# contact_control_board.net
KiCad netlist of a schematic drawn in EAGLE
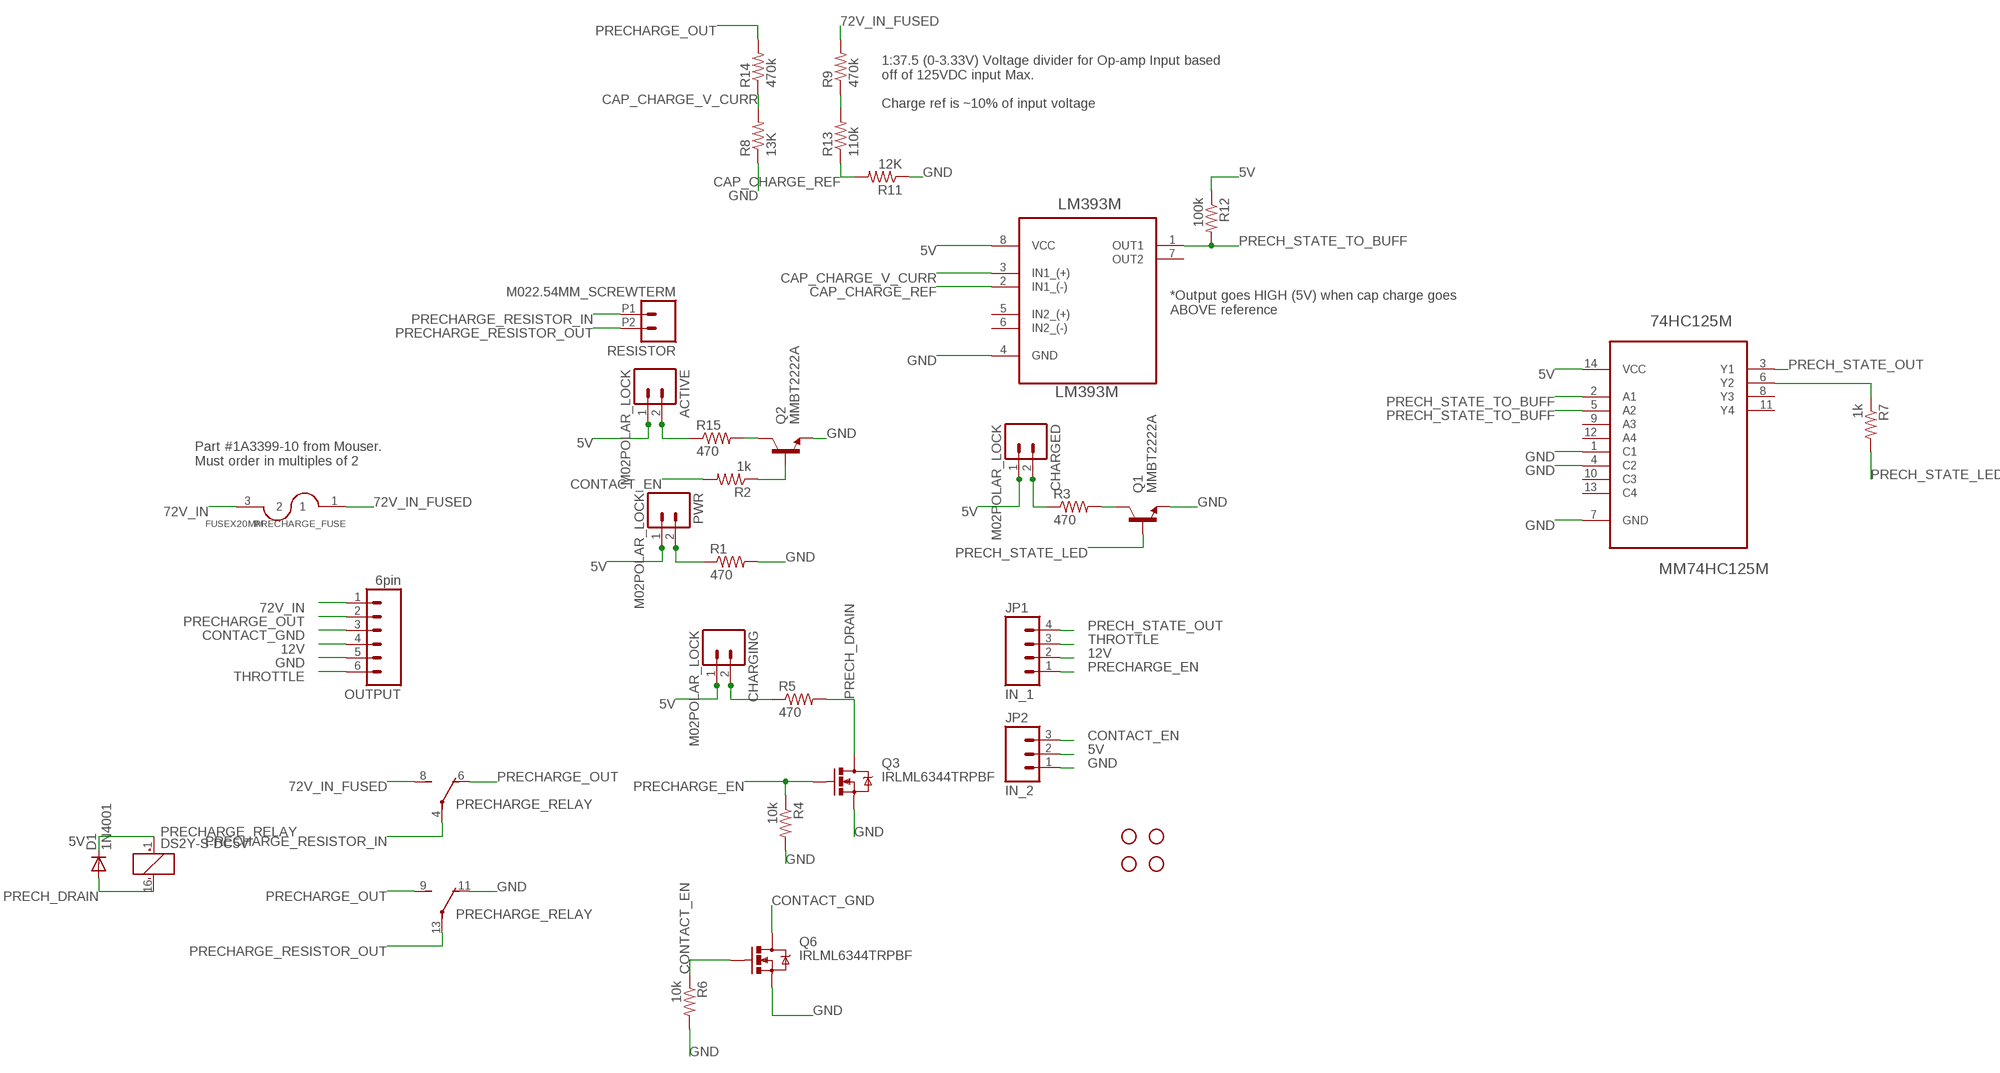
[diagram p0: schematic, sheet 1]

(export (version "E")
  (design (tool "Eeschema 10.0.6"))
  (components
    (comp (ref "74HC125M")
      (value "MM74HC125M")
      (footprint "eagle-import:SOIC127P600X175-14N")
      (libsource (lib "eagle-import") (part "MM74HC125M"))
    )
    (comp (ref "ACTIVE")
      (value "M02POLAR_LOCK")
      (footprint "eagle-import:MOLEX-1X2_LOCK")
      (libsource (lib "eagle-import") (part "M02POLAR_LOCK"))
    )
    (comp (ref "CHARGED")
      (value "M02POLAR_LOCK")
      (footprint "eagle-import:MOLEX-1X2_LOCK")
      (libsource (lib "eagle-import") (part "M02POLAR_LOCK"))
    )
    (comp (ref "CHARGING")
      (value "M02POLAR_LOCK")
      (footprint "eagle-import:MOLEX-1X2_LOCK")
      (libsource (lib "eagle-import") (part "M02POLAR_LOCK"))
    )
    (comp (ref "D1")
      (value "1N4001")
      (footprint "eagle-import:DIODE-1N4001")
      (libsource (lib "eagle-import") (part "DIODEPTH"))
    )
    (comp (ref "JP1")
      (value "IN_1")
      (footprint "eagle-import:MOLEX-1X4_LOCK")
      (libsource (lib "eagle-import") (part "M04POLAR_LOCK"))
    )
    (comp (ref "JP2")
      (value "IN_2")
      (footprint "eagle-import:MOLEX-1X3_LOCK")
      (libsource (lib "eagle-import") (part "M03POLAR_LOCK"))
    )
    (comp (ref "LM393M")
      (value "LM393M")
      (footprint "eagle-import:SOIC127P600X180-8N")
      (libsource (lib "eagle-import") (part "LM393M"))
    )
    (comp (ref "OUTPUT")
      (value "6pin")
      (footprint "eagle-import:SCREWTERMINAL-3.5MM-6")
      (libsource (lib "eagle-import") (part "M063.5MM-6"))
    )
    (comp (ref "PRECHARGE_FUSE")
      (value "FUSEX20MM")
      (footprint "eagle-import:FUSE_5MM")
      (libsource (lib "eagle-import") (part "FUSEX20MM"))
    )
    (comp (ref "PRECHARGE_RELAY")
      (value "DS2Y-S-DC5V")
      (footprint "eagle-import:DS2Y")
      (libsource (lib "eagle-import") (part "DS2Y-S-DC5V"))
    )
    (comp (ref "PWR")
      (value "M02POLAR_LOCK")
      (footprint "eagle-import:MOLEX-1X2_LOCK")
      (libsource (lib "eagle-import") (part "M02POLAR_LOCK"))
    )
    (comp (ref "Q1")
      (value "MMBT2222A")
      (footprint "eagle-import:SOT23")
      (libsource (lib "eagle-import") (part "TRANSISTOR_NPNMMBT2222A"))
    )
    (comp (ref "Q2")
      (value "MMBT2222A")
      (footprint "eagle-import:SOT23")
      (libsource (lib "eagle-import") (part "TRANSISTOR_NPNMMBT2222A"))
    )
    (comp (ref "Q3")
      (value "IRLML6344TRPBF")
      (footprint "eagle-import:SOT23")
      (libsource (lib "eagle-import") (part "MOSFET-NCHANNELBSS123LT1G"))
    )
    (comp (ref "Q6")
      (value "IRLML6344TRPBF")
      (footprint "eagle-import:SOT23")
      (libsource (lib "eagle-import") (part "MOSFET-NCHANNELBSS123LT1G"))
    )
    (comp (ref "R1")
      (value "470")
      (footprint "eagle-import:0805")
      (libsource (lib "eagle-import") (part "RESISTOR0805-RES"))
    )
    (comp (ref "R2")
      (value "1k")
      (footprint "eagle-import:0603-RES")
      (libsource (lib "eagle-import") (part "RESISTOR0603-RES"))
    )
    (comp (ref "R3")
      (value "470")
      (footprint "eagle-import:0805")
      (libsource (lib "eagle-import") (part "RESISTOR0805-RES"))
    )
    (comp (ref "R4")
      (value "10k")
      (footprint "eagle-import:0603-RES")
      (libsource (lib "eagle-import") (part "RESISTOR0603-RES"))
    )
    (comp (ref "R5")
      (value "470")
      (footprint "eagle-import:0805")
      (libsource (lib "eagle-import") (part "RESISTOR0805-RES"))
    )
    (comp (ref "R6")
      (value "10k")
      (footprint "eagle-import:0603-RES")
      (libsource (lib "eagle-import") (part "RESISTOR0603-RES"))
    )
    (comp (ref "R7")
      (value "1k")
      (footprint "eagle-import:0603-RES")
      (libsource (lib "eagle-import") (part "RESISTOR0603-RES"))
    )
    (comp (ref "R8")
      (value "13K")
      (footprint "eagle-import:0805")
      (libsource (lib "eagle-import") (part "RESISTOR0805-RES"))
    )
    (comp (ref "R9")
      (value "470k")
      (footprint "eagle-import:0805")
      (libsource (lib "eagle-import") (part "RESISTOR0805-RES"))
    )
    (comp (ref "R11")
      (value "12K")
      (footprint "eagle-import:0805")
      (libsource (lib "eagle-import") (part "RESISTOR0805-RES"))
    )
    (comp (ref "R12")
      (value "100k")
      (footprint "eagle-import:0603-RES")
      (libsource (lib "eagle-import") (part "RESISTOR0603-RES"))
    )
    (comp (ref "R13")
      (value "110k")
      (footprint "eagle-import:0805")
      (libsource (lib "eagle-import") (part "RESISTOR0805-RES"))
    )
    (comp (ref "R14")
      (value "470k")
      (footprint "eagle-import:0805")
      (libsource (lib "eagle-import") (part "RESISTOR0805-RES"))
    )
    (comp (ref "R15")
      (value "470")
      (footprint "eagle-import:0805")
      (libsource (lib "eagle-import") (part "RESISTOR0805-RES"))
    )
    (comp (ref "RESISTOR")
      (value "M022.54MM_SCREWTERM")
      (footprint "eagle-import:1X02_2.54_SCREWTERM")
      (libsource (lib "eagle-import") (part "M022.54MM_SCREWTERM"))
    )
    (comp (ref "STANDOFF1")
      (value "STAND-OFF")
      (footprint "eagle-import:STAND-OFF")
      (libsource (lib "eagle-import") (part "STAND-OFF"))
    )
    (comp (ref "STANDOFF2")
      (value "STAND-OFF")
      (footprint "eagle-import:STAND-OFF")
      (libsource (lib "eagle-import") (part "STAND-OFF"))
    )
    (comp (ref "STANDOFF3")
      (value "STAND-OFF")
      (footprint "eagle-import:STAND-OFF")
      (libsource (lib "eagle-import") (part "STAND-OFF"))
    )
    (comp (ref "STANDOFF4")
      (value "STAND-OFF")
      (footprint "eagle-import:STAND-OFF")
      (libsource (lib "eagle-import") (part "STAND-OFF"))
    )
  )
  (nets
    (net (code "1") (name "/5V") (class "Default")
      (node (ref "74HC125M") (pin "14") (pinfunction "VCC_14") (pintype "power_in"))
      (node (ref "ACTIVE") (pin "1") (pinfunction "1_1") (pintype "passive"))
      (node (ref "CHARGED") (pin "1") (pinfunction "1_1") (pintype "passive"))
      (node (ref "CHARGING") (pin "1") (pinfunction "1_1") (pintype "passive"))
      (node (ref "D1") (pin "C") (pinfunction "C_C") (pintype "passive"))
      (node (ref "JP2") (pin "2") (pinfunction "2_2") (pintype "passive"))
      (node (ref "LM393M") (pin "8") (pinfunction "VCC_8") (pintype "power_in"))
      (node (ref "PRECHARGE_RELAY") (pin "1") (pinfunction "+_1") (pintype "passive"))
      (node (ref "PWR") (pin "1") (pinfunction "1_1") (pintype "passive"))
      (node (ref "R12") (pin "1") (pinfunction "1_1") (pintype "passive"))
    )
    (net (code "2") (name "/12V") (class "Default")
      (node (ref "JP1") (pin "2") (pinfunction "2_2") (pintype "passive"))
      (node (ref "OUTPUT") (pin "4") (pinfunction "4_4") (pintype "passive"))
    )
    (net (code "3") (name "/72V_IN") (class "Default")
      (node (ref "OUTPUT") (pin "1") (pinfunction "1_1") (pintype "passive"))
      (node (ref "PRECHARGE_FUSE") (pin "3") (pinfunction "2_3") (pintype "bidirectional"))
    )
    (net (code "4") (name "/72V_IN_FUSED") (class "Default")
      (node (ref "PRECHARGE_FUSE") (pin "1") (pinfunction "1_1") (pintype "bidirectional"))
      (node (ref "PRECHARGE_RELAY") (pin "8") (pinfunction "S_8") (pintype "passive"))
      (node (ref "R9") (pin "2") (pinfunction "2_2") (pintype "passive"))
    )
    (net (code "5") (name "/CAP_CHARGE_REF") (class "Default")
      (node (ref "LM393M") (pin "2") (pinfunction "IN1_(-)_2") (pintype "input"))
      (node (ref "R11") (pin "2") (pinfunction "2_2") (pintype "passive"))
      (node (ref "R13") (pin "1") (pinfunction "1_1") (pintype "passive"))
    )
    (net (code "6") (name "/CAP_CHARGE_V_CURR") (class "Default")
      (node (ref "LM393M") (pin "3") (pinfunction "IN1_(+)_3") (pintype "input"))
      (node (ref "R14") (pin "1") (pinfunction "1_1") (pintype "passive"))
      (node (ref "R8") (pin "2") (pinfunction "2_2") (pintype "passive"))
    )
    (net (code "7") (name "/CONTACT_EN") (class "Default")
      (node (ref "JP2") (pin "3") (pinfunction "3_3") (pintype "passive"))
      (node (ref "Q6") (pin "1") (pinfunction "G_1") (pintype "passive"))
      (node (ref "R2") (pin "2") (pinfunction "2_2") (pintype "passive"))
      (node (ref "R6") (pin "1") (pinfunction "1_1") (pintype "passive"))
    )
    (net (code "8") (name "/CONTACT_GND") (class "Default")
      (node (ref "OUTPUT") (pin "3") (pinfunction "3_3") (pintype "passive"))
      (node (ref "Q6") (pin "3") (pinfunction "D_3") (pintype "passive"))
    )
    (net (code "9") (name "/GND") (class "Default")
      (node (ref "74HC125M") (pin "1") (pinfunction "C1_1") (pintype "input"))
      (node (ref "74HC125M") (pin "4") (pinfunction "C2_4") (pintype "input"))
      (node (ref "74HC125M") (pin "7") (pinfunction "GND_7") (pintype "passive"))
      (node (ref "JP2") (pin "1") (pinfunction "1_1") (pintype "passive"))
      (node (ref "LM393M") (pin "4") (pinfunction "GND_4") (pintype "passive"))
      (node (ref "OUTPUT") (pin "5") (pinfunction "5_5") (pintype "passive"))
      (node (ref "PRECHARGE_RELAY") (pin "11") (pinfunction "O_11") (pintype "passive"))
      (node (ref "Q1") (pin "2") (pinfunction "E_2") (pintype "passive"))
      (node (ref "Q2") (pin "2") (pinfunction "E_2") (pintype "passive"))
      (node (ref "Q3") (pin "2") (pinfunction "S_2") (pintype "passive"))
      (node (ref "Q6") (pin "2") (pinfunction "S_2") (pintype "passive"))
      (node (ref "R1") (pin "2") (pinfunction "2_2") (pintype "passive"))
      (node (ref "R11") (pin "1") (pinfunction "1_1") (pintype "passive"))
      (node (ref "R4") (pin "2") (pinfunction "2_2") (pintype "passive"))
      (node (ref "R6") (pin "2") (pinfunction "2_2") (pintype "passive"))
      (node (ref "R8") (pin "1") (pinfunction "1_1") (pintype "passive"))
    )
    (net (code "10") (name "/PRECHARGE_EN") (class "Default")
      (node (ref "JP1") (pin "1") (pinfunction "1_1") (pintype "passive"))
      (node (ref "Q3") (pin "1") (pinfunction "G_1") (pintype "passive"))
      (node (ref "R4") (pin "1") (pinfunction "1_1") (pintype "passive"))
    )
    (net (code "11") (name "/PRECHARGE_OUT") (class "Default")
      (node (ref "OUTPUT") (pin "2") (pinfunction "2_2") (pintype "passive"))
      (node (ref "PRECHARGE_RELAY") (pin "6") (pinfunction "O_6") (pintype "passive"))
      (node (ref "PRECHARGE_RELAY") (pin "9") (pinfunction "S_9") (pintype "passive"))
      (node (ref "R14") (pin "2") (pinfunction "2_2") (pintype "passive"))
    )
    (net (code "12") (name "/PRECHARGE_RESISTOR_IN") (class "Default")
      (node (ref "PRECHARGE_RELAY") (pin "4") (pinfunction "P_4") (pintype "passive"))
      (node (ref "RESISTOR") (pin "P1") (pinfunction "1_P1") (pintype "passive"))
    )
    (net (code "13") (name "/PRECHARGE_RESISTOR_OUT") (class "Default")
      (node (ref "PRECHARGE_RELAY") (pin "13") (pinfunction "P_13") (pintype "passive"))
      (node (ref "RESISTOR") (pin "P2") (pinfunction "2_P2") (pintype "passive"))
    )
    (net (code "14") (name "/PRECH_DRAIN") (class "Default")
      (node (ref "D1") (pin "A") (pinfunction "A_A") (pintype "passive"))
      (node (ref "PRECHARGE_RELAY") (pin "16") (pinfunction "-_16") (pintype "passive"))
      (node (ref "Q3") (pin "3") (pinfunction "D_3") (pintype "passive"))
      (node (ref "R5") (pin "2") (pinfunction "2_2") (pintype "passive"))
    )
    (net (code "15") (name "/PRECH_STATE_LED") (class "Default")
      (node (ref "Q1") (pin "1") (pinfunction "B_1") (pintype "passive"))
      (node (ref "R7") (pin "2") (pinfunction "2_2") (pintype "passive"))
    )
    (net (code "16") (name "/PRECH_STATE_OUT") (class "Default")
      (node (ref "74HC125M") (pin "3") (pinfunction "Y1_3") (pintype "output"))
      (node (ref "JP1") (pin "4") (pinfunction "4_4") (pintype "passive"))
    )
    (net (code "17") (name "/PRECH_STATE_TO_BUFF") (class "Default")
      (node (ref "74HC125M") (pin "2") (pinfunction "A1_2") (pintype "input"))
      (node (ref "74HC125M") (pin "5") (pinfunction "A2_5") (pintype "input"))
      (node (ref "LM393M") (pin "1") (pinfunction "OUT1_1") (pintype "output"))
      (node (ref "R12") (pin "2") (pinfunction "2_2") (pintype "passive"))
    )
    (net (code "18") (name "/THROTTLE") (class "Default")
      (node (ref "JP1") (pin "3") (pinfunction "3_3") (pintype "passive"))
      (node (ref "OUTPUT") (pin "6") (pinfunction "6_6") (pintype "passive"))
    )
    (net (code "19") (name "Net-(74HC125M-Y2)") (class "Default")
      (node (ref "74HC125M") (pin "6") (pinfunction "Y2_6") (pintype "output"))
      (node (ref "R7") (pin "1") (pinfunction "1_1") (pintype "passive"))
    )
    (net (code "20") (name "Net-(ACTIVE-Pad2)") (class "Default")
      (node (ref "ACTIVE") (pin "2") (pinfunction "2_2") (pintype "passive"))
      (node (ref "R15") (pin "1") (pinfunction "1_1") (pintype "passive"))
    )
    (net (code "21") (name "Net-(CHARGED-Pad2)") (class "Default")
      (node (ref "CHARGED") (pin "2") (pinfunction "2_2") (pintype "passive"))
      (node (ref "R3") (pin "1") (pinfunction "1_1") (pintype "passive"))
    )
    (net (code "22") (name "Net-(CHARGING-Pad2)") (class "Default")
      (node (ref "CHARGING") (pin "2") (pinfunction "2_2") (pintype "passive"))
      (node (ref "R5") (pin "1") (pinfunction "1_1") (pintype "passive"))
    )
    (net (code "23") (name "Net-(PWR-Pad2)") (class "Default")
      (node (ref "PWR") (pin "2") (pinfunction "2_2") (pintype "passive"))
      (node (ref "R1") (pin "1") (pinfunction "1_1") (pintype "passive"))
    )
    (net (code "24") (name "Net-(Q1-C)") (class "Default")
      (node (ref "Q1") (pin "3") (pinfunction "C_3") (pintype "passive"))
      (node (ref "R3") (pin "2") (pinfunction "2_2") (pintype "passive"))
    )
    (net (code "25") (name "Net-(Q2-B)") (class "Default")
      (node (ref "Q2") (pin "1") (pinfunction "B_1") (pintype "passive"))
      (node (ref "R2") (pin "1") (pinfunction "1_1") (pintype "passive"))
    )
    (net (code "26") (name "Net-(Q2-C)") (class "Default")
      (node (ref "Q2") (pin "3") (pinfunction "C_3") (pintype "passive"))
      (node (ref "R15") (pin "2") (pinfunction "2_2") (pintype "passive"))
    )
    (net (code "27") (name "Net-(R13-Pad2)") (class "Default")
      (node (ref "R13") (pin "2") (pinfunction "2_2") (pintype "passive"))
      (node (ref "R9") (pin "1") (pinfunction "1_1") (pintype "passive"))
    )
    (net (code "28") (name "unconnected-(74HC125M-A3-Pad9)") (class "Default")
      (node (ref "74HC125M") (pin "9") (pinfunction "A3_9") (pintype "input"))
    )
    (net (code "29") (name "unconnected-(74HC125M-A4-Pad12)") (class "Default")
      (node (ref "74HC125M") (pin "12") (pinfunction "A4_12") (pintype "input"))
    )
    (net (code "30") (name "unconnected-(74HC125M-C3-Pad10)") (class "Default")
      (node (ref "74HC125M") (pin "10") (pinfunction "C3_10") (pintype "input"))
    )
    (net (code "31") (name "unconnected-(74HC125M-C4-Pad13)") (class "Default")
      (node (ref "74HC125M") (pin "13") (pinfunction "C4_13") (pintype "input"))
    )
    (net (code "32") (name "unconnected-(74HC125M-Y3-Pad8)") (class "Default")
      (node (ref "74HC125M") (pin "8") (pinfunction "Y3_8") (pintype "output"))
    )
    (net (code "33") (name "unconnected-(74HC125M-Y4-Pad11)") (class "Default")
      (node (ref "74HC125M") (pin "11") (pinfunction "Y4_11") (pintype "output"))
    )
    (net (code "34") (name "unconnected-(LM393M-IN2_(+)-Pad5)") (class "Default")
      (node (ref "LM393M") (pin "5") (pinfunction "IN2_(+)_5") (pintype "input"))
    )
    (net (code "35") (name "unconnected-(LM393M-IN2_(-)-Pad6)") (class "Default")
      (node (ref "LM393M") (pin "6") (pinfunction "IN2_(-)_6") (pintype "input"))
    )
    (net (code "36") (name "unconnected-(LM393M-OUT2-Pad7)") (class "Default")
      (node (ref "LM393M") (pin "7") (pinfunction "OUT2_7") (pintype "output"))
    )
  )
)
